# 33-SOC_GENERAL_AND_MCU_GENERAL.net
KiCad netlist of a schematic drawn in Altium Designer
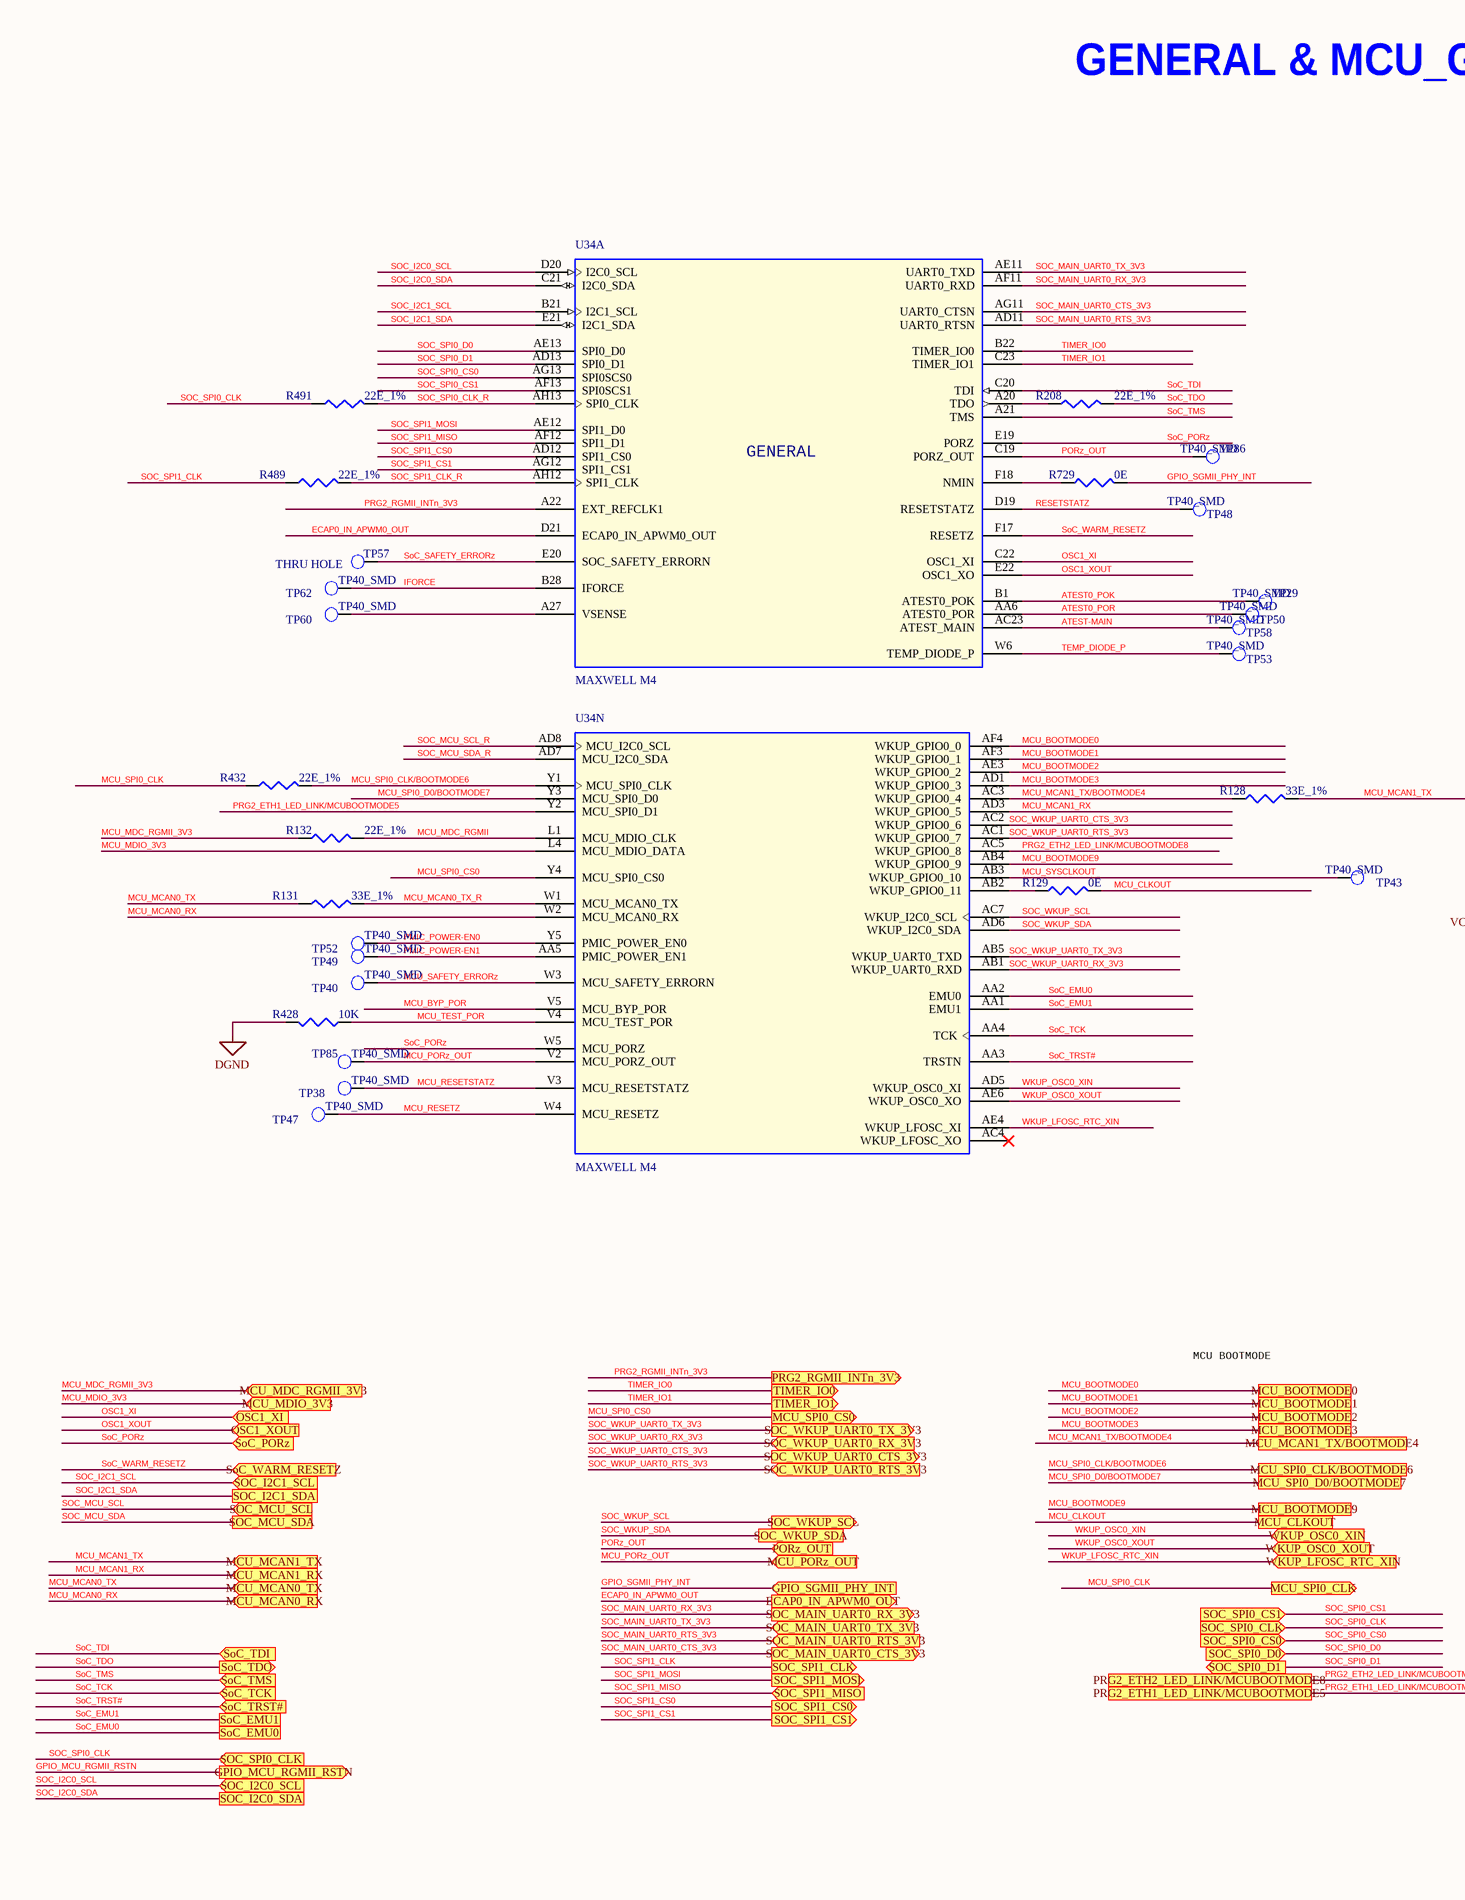
[diagram p0: 33-SOC_GENERAL AND MCU GENERAL.SchDoc, left]
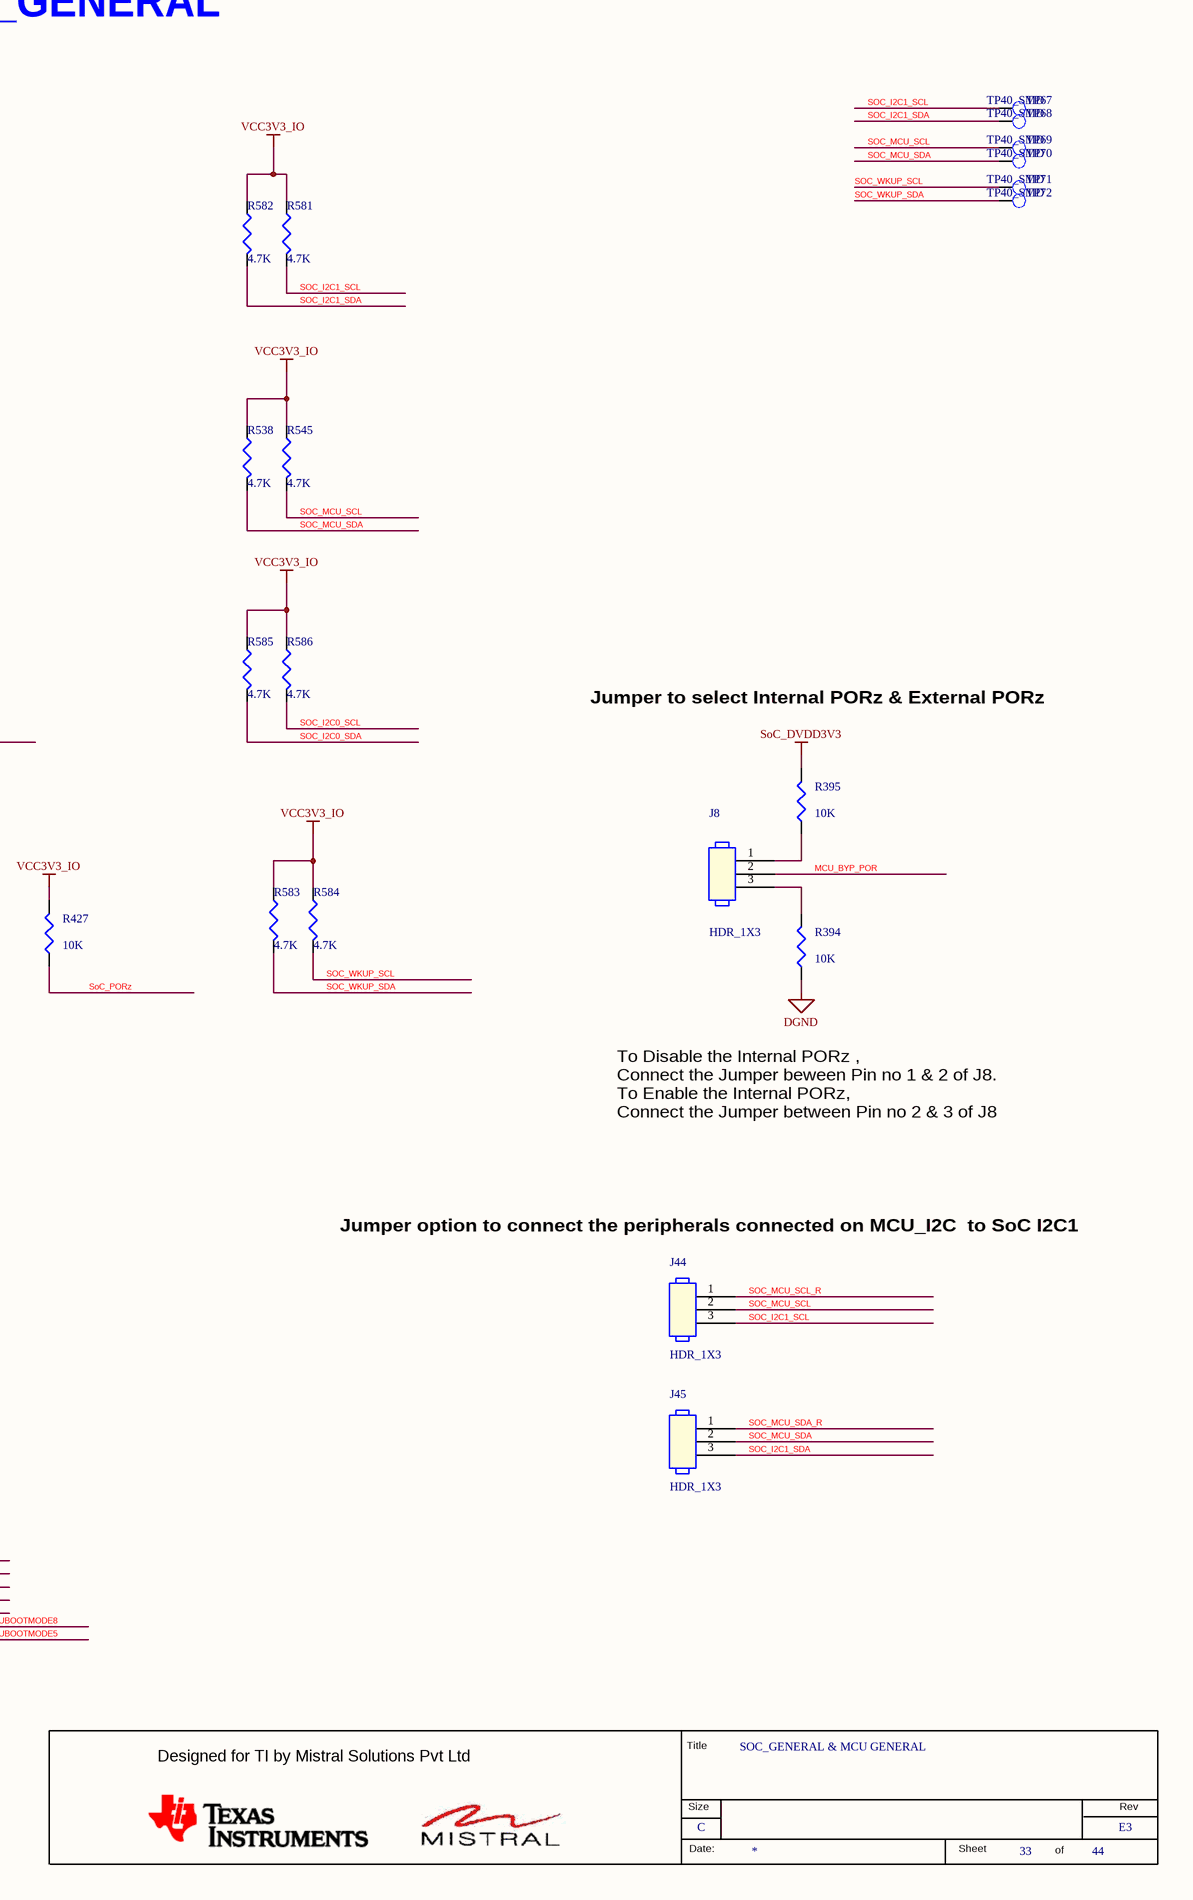
[diagram p1: 33-SOC_GENERAL AND MCU GENERAL.SchDoc, right]

(export (version "E")
  (design (tool "Eeschema 10.0.6"))
  (components
    (comp (ref "J8")
      (value "HDR_1X3")
      (footprint "HDR_3X1_100_S_T")
      (description "HDR 1X3 2.54MM PITCH ST TH")
      (fields (field (name "DISTRIBUTOR_PART_NUMBER") "609-3471-ND") (field (name "VOLTAGE") "NA"))
      (libsource (lib "*") (part "HEADER_3X1"))
    )
    (comp (ref "J44")
      (value "HDR_1X3")
      (footprint "HDR_3X1_100_S_T")
      (description "HDR 1X3 2.54MM PITCH ST TH")
      (fields (field (name "DISTRIBUTOR_PART_NUMBER") "609-3471-ND") (field (name "VOLTAGE") "NA"))
      (libsource (lib "*") (part "HEADER_3X1"))
    )
    (comp (ref "J45")
      (value "HDR_1X3")
      (footprint "HDR_3X1_100_S_T")
      (description "HDR 1X3 2.54MM PITCH ST TH")
      (fields
        (field (name "MISTRAL PART NO") "150016060025-R")
        (field (name "MFR_PART_NUMBER") "68001-403HLF")
      )
      (libsource (lib "*") (part "HEADER_3X1"))
    )
    (comp (ref "R128")
      (value "33E_1%")
      (footprint "RES0402_0-5")
      (description "RES 33E 1/16W 1% 0402")
      (fields (field (name "DISTRIBUTOR_PART_NUMBER") "P33.0LCT-ND") (field (name "VOLTAGE") "NA"))
      (libsource (lib "*") (part "RESISTOR_Dup5"))
    )
    (comp (ref "R129")
      (value "0E")
      (footprint "RES0402_0-5")
      (description "RES 0E 1/16W 0402")
      (fields
        (field (name "MISTRAL PART NO") "110010080019-P")
        (field (name "MFR_PART_NUMBER") "CRCW04020000Z0ED")
      )
      (libsource (lib "*") (part "RESISTOR_Dup4"))
    )
    (comp (ref "R131")
      (value "33E_1%")
      (footprint "RES0402_0-5")
      (description "RES 33E 1/16W 1% 0402")
      (fields
        (field (name "MISTRAL PART NO") "110014110006-R")
        (field (name "MFR_PART_NUMBER") "ERJ-2RKF33R0X")
      )
      (libsource (lib "*") (part "RESISTOR_Dup5"))
    )
    (comp (ref "R132")
      (value "22E_1%")
      (footprint "RES0402")
      (description "RES 22E 1/16W 1% 0402")
      (fields
        (field (name "MISTRAL PART NO") "110009090004-P")
        (field (name "MFR_PART_NUMBER") "RC0402FR-0722RL")
      )
      (libsource (lib "*") (part "RESISTOR_Dup5"))
    )
    (comp (ref "R208")
      (value "22E_1%")
      (footprint "RES0402")
      (description "RES 22E 1/16W 1% 0402")
      (fields
        (field (name "CUST_PART_NUMBER") "4700-80047E")
        (field (name "DISTRIBUTOR_PART_NUMBER") "311-22.0LRCT-ND")
      )
      (libsource (lib "*") (part "RESISTOR_Dup4"))
    )
    (comp (ref "R394")
      (value "10K")
      (footprint "RES0402_0-5")
      (description "RES 10K 1/16W 5% 0402")
      (fields (field (name "DISTRIBUTOR_PART_NUMBER") "311-10KJRCT-ND") (field (name "VOLTAGE") "NA"))
      (libsource (lib "*") (part "RESISTOR_Dup5"))
    )
    (comp (ref "R395")
      (value "10K")
      (footprint "RES0402_0-5")
      (description "RES 10K 1/16W 5% 0402")
      (fields (field (name "DISTRIBUTOR_PART_NUMBER") "311-10KJRCT-ND") (field (name "VOLTAGE") "NA"))
      (libsource (lib "*") (part "RESISTOR_Dup5"))
    )
    (comp (ref "R427")
      (value "10K")
      (footprint "RES0402_0-5")
      (description "RES 10K 1/16W 5% 0402")
      (fields
        (field (name "MISTRAL PART NO") "110009030208-R")
        (field (name "MFR_PART_NUMBER") "RC0402JR-0710KL")
      )
      (libsource (lib "*") (part "RESISTOR_Dup5"))
    )
    (comp (ref "R428")
      (value "10K")
      (footprint "RES0402_0-5")
      (description "RES 10K 1/16W 5% 0402")
      (fields
        (field (name "MISTRAL PART NO") "110009030208-R")
        (field (name "MFR_PART_NUMBER") "RC0402JR-0710KL")
      )
      (libsource (lib "*") (part "RESISTOR_Dup5"))
    )
    (comp (ref "R432")
      (value "22E_1%")
      (footprint "RES0402")
      (description "RES 22E 1/16W 1% 0402")
      (fields
        (field (name "MISTRAL PART NO") "110009090004-P")
        (field (name "MFR_PART_NUMBER") "RC0402FR-0722RL")
      )
      (libsource (lib "*") (part "RESISTOR_Dup4"))
    )
    (comp (ref "R489")
      (value "22E_1%")
      (footprint "RES0402")
      (description "RES 22E 1/16W 1% 0402")
      (fields
        (field (name "CUST_PART_NUMBER") "4700-80047E")
        (field (name "DISTRIBUTOR_PART_NUMBER") "311-22.0LRCT-ND")
      )
      (libsource (lib "*") (part "RESISTOR_Dup4"))
    )
    (comp (ref "R491")
      (value "22E_1%")
      (footprint "RES0402")
      (description "RES 22E 1/16W 1% 0402")
      (fields
        (field (name "CUST_PART_NUMBER") "4700-80047E")
        (field (name "DISTRIBUTOR_PART_NUMBER") "311-22.0LRCT-ND")
      )
      (libsource (lib "*") (part "RESISTOR_Dup4"))
    )
    (comp (ref "R538")
      (value "4.7K")
      (footprint "RES0402")
      (description "RES 4.7K 1/16W 5% 0402")
      (fields (field (name "DISTRIBUTOR_PART_NUMBER") "311-4.7KJRCT-ND") (field (name "VOLTAGE") "NA"))
      (libsource (lib "*") (part "RESISTOR_Dup5"))
    )
    (comp (ref "R545")
      (value "4.7K")
      (footprint "RES0402")
      (description "RES 4.7K 1/16W 5% 0402")
      (fields
        (field (name "MISTRAL PART NO") "110009030792-R")
        (field (name "MFR_PART_NUMBER") "RC0402JR-074K7L")
      )
      (libsource (lib "*") (part "RESISTOR_Dup5"))
    )
    (comp (ref "R581")
      (value "4.7K")
      (footprint "RES0402")
      (description "RES 4.7K 1/16W 5% 0402")
      (fields
        (field (name "MISTRAL PART NO") "110009030792-R")
        (field (name "MFR_PART_NUMBER") "RC0402JR-074K7L")
      )
      (libsource (lib "*") (part "RESISTOR_Dup5"))
    )
    (comp (ref "R582")
      (value "4.7K")
      (footprint "RES0402")
      (description "RES 4.7K 1/16W 5% 0402")
      (fields (field (name "DISTRIBUTOR_PART_NUMBER") "311-4.7KJRCT-ND") (field (name "VOLTAGE") "NA"))
      (libsource (lib "*") (part "RESISTOR_Dup5"))
    )
    (comp (ref "R583")
      (value "4.7K")
      (footprint "RES0402")
      (description "RES 4.7K 1/16W 5% 0402")
      (fields
        (field (name "MISTRAL PART NO") "110009030792-R")
        (field (name "MFR_PART_NUMBER") "RC0402JR-074K7L")
      )
      (libsource (lib "*") (part "RESISTOR_Dup5"))
    )
    (comp (ref "R584")
      (value "4.7K")
      (footprint "RES0402")
      (description "RES 4.7K 1/16W 5% 0402")
      (fields (field (name "DISTRIBUTOR_PART_NUMBER") "311-4.7KJRCT-ND") (field (name "VOLTAGE") "NA"))
      (libsource (lib "*") (part "RESISTOR_Dup5"))
    )
    (comp (ref "R585")
      (value "4.7K")
      (footprint "RES0402")
      (description "RES 4.7K 1/16W 5% 0402")
      (fields (field (name "DISTRIBUTOR_PART_NUMBER") "311-4.7KJRCT-ND") (field (name "VOLTAGE") "NA"))
      (libsource (lib "*") (part "RESISTOR_Dup5"))
    )
    (comp (ref "R586")
      (value "4.7K")
      (footprint "RES0402")
      (description "RES 4.7K 1/16W 5% 0402")
      (fields
        (field (name "MISTRAL PART NO") "110009030792-R")
        (field (name "MFR_PART_NUMBER") "RC0402JR-074K7L")
      )
      (libsource (lib "*") (part "RESISTOR_Dup5"))
    )
    (comp (ref "R729")
      (value "0E")
      (footprint "RES0402_0-5")
      (description "RES 0E 1/16W 0402")
      (fields (field (name "DISTRIBUTOR_PART_NUMBER") "541-0.0JCT-ND") (field (name "VOLTAGE") "NA"))
      (libsource (lib "*") (part "RESISTOR_Dup5"))
    )
    (comp (ref "TP29")
      (value "TP40_SMD")
      (footprint "TP40_SMD")
      (description "TESTPOINT CIR 40 SMD")
      (fields (field (name "MISTRAL PART NO") "130009030933") (field (name "DISTRIBUTOR_PART_NUMBER") "NA"))
      (libsource (lib "*") (part "TESTPOINT"))
    )
    (comp (ref "TP38")
      (value "TP40_SMD")
      (footprint "TP40_SMD")
      (description "TESTPOINT CIR 40 SMD")
      (fields (field (name "MISTRAL PART NO") "130009030933") (field (name "DISTRIBUTOR_PART_NUMBER") "NA"))
      (libsource (lib "*") (part "TESTPOINT"))
    )
    (comp (ref "TP40")
      (value "TP40_SMD")
      (footprint "TP40_SMD")
      (description "TESTPOINT CIR 40 SMD")
      (fields (field (name "MISTRAL PART NO") "130009030933") (field (name "DISTRIBUTOR_PART_NUMBER") "NA"))
      (libsource (lib "*") (part "TESTPOINT"))
    )
    (comp (ref "TP43")
      (value "TP40_SMD")
      (footprint "TP40_SMD")
      (description "TESTPOINT CIR 40 SMD")
      (fields (field (name "DISTRIBUTOR_PART_NUMBER") "NA") (field (name "MISTRAL PART NO") "130009030933"))
      (libsource (lib "*") (part "TESTPOINT"))
    )
    (comp (ref "TP47")
      (value "TP40_SMD")
      (footprint "TP40_SMD")
      (description "TESTPOINT CIR 40 SMD")
      (fields (field (name "MISTRAL PART NO") "130009030933") (field (name "DISTRIBUTOR_PART_NUMBER") "NA"))
      (libsource (lib "*") (part "TESTPOINT"))
    )
    (comp (ref "TP48")
      (value "TP40_SMD")
      (footprint "TP40_SMD")
      (description "TESTPOINT CIR 40 SMD")
      (fields (field (name "MISTRAL PART NO") "130009030933") (field (name "DISTRIBUTOR_PART_NUMBER") "NA"))
      (libsource (lib "*") (part "TESTPOINT"))
    )
    (comp (ref "TP49")
      (value "TP40_SMD")
      (footprint "TP40_SMD")
      (description "TESTPOINT CIR 40 SMD")
      (fields (field (name "VOLTAGE") "NA") (field (name "MISTRAL PART NO") "130009030933"))
      (libsource (lib "*") (part "TESTPOINT"))
    )
    (comp (ref "TP50")
      (value "TP40_SMD")
      (footprint "TP40_SMD")
      (description "TESTPOINT CIR 40 SMD")
      (fields (field (name "VOLTAGE") "NA") (field (name "MISTRAL PART NO") "130009030933"))
      (libsource (lib "*") (part "TESTPOINT"))
    )
    (comp (ref "TP52")
      (value "TP40_SMD")
      (footprint "TP40_SMD")
      (description "TESTPOINT CIR 40 SMD")
      (fields (field (name "MISTRAL PART NO") "130009030933") (field (name "DISTRIBUTOR_PART_NUMBER") "NA"))
      (libsource (lib "*") (part "TESTPOINT"))
    )
    (comp (ref "TP53")
      (value "TP40_SMD")
      (footprint "TP40_SMD")
      (description "TESTPOINT CIR 40 SMD")
      (fields (field (name "VOLTAGE") "NA") (field (name "MISTRAL PART NO") "130009030933"))
      (libsource (lib "*") (part "TESTPOINT"))
    )
    (comp (ref "TP57")
      (value "THRU HOLE")
      (footprint "TP_40X65")
      (description "TESTPOINT 1.0MM DRILL PTH")
      (fields (field (name "DISTRIBUTOR_PART_NUMBER") "NA") (field (name "MFR_PART_NUMBER") "TP_40X65"))
      (libsource (lib "*") (part "TESTPOINT"))
    )
    (comp (ref "TP58")
      (value "TP40_SMD")
      (footprint "TP40_SMD")
      (description "TESTPOINT CIR 40 SMD")
      (fields (field (name "VOLTAGE") "NA") (field (name "MISTRAL PART NO") "130009030933"))
      (libsource (lib "*") (part "TESTPOINT"))
    )
    (comp (ref "TP60")
      (value "TP40_SMD")
      (footprint "TP40_SMD")
      (description "TESTPOINT CIR 40 SMD")
      (fields (field (name "VOLTAGE") "NA") (field (name "MISTRAL PART NO") "130009030933"))
      (libsource (lib "*") (part "TESTPOINT"))
    )
    (comp (ref "TP62")
      (value "TP40_SMD")
      (footprint "TP40_SMD")
      (description "TESTPOINT CIR 40 SMD")
      (fields (field (name "VOLTAGE") "NA") (field (name "MISTRAL PART NO") "130009030933"))
      (libsource (lib "*") (part "TESTPOINT"))
    )
    (comp (ref "TP67")
      (value "TP40_SMD")
      (footprint "TP40_SMD")
      (description "TESTPOINT CIR 40 SMD")
      (fields (field (name "MISTRAL PART NO") "130009030933") (field (name "DISTRIBUTOR_PART_NUMBER") "NA"))
      (libsource (lib "*") (part "TESTPOINT"))
    )
    (comp (ref "TP68")
      (value "TP40_SMD")
      (footprint "TP40_SMD")
      (description "TESTPOINT CIR 40 SMD")
      (fields (field (name "VOLTAGE") "NA") (field (name "MISTRAL PART NO") "130009030933"))
      (libsource (lib "*") (part "TESTPOINT"))
    )
    (comp (ref "TP69")
      (value "TP40_SMD")
      (footprint "TP40_SMD")
      (description "TESTPOINT CIR 40 SMD")
      (fields (field (name "VOLTAGE") "NA") (field (name "MISTRAL PART NO") "130009030933"))
      (libsource (lib "*") (part "TESTPOINT"))
    )
    (comp (ref "TP70")
      (value "TP40_SMD")
      (footprint "TP40_SMD")
      (description "TESTPOINT CIR 40 SMD")
      (fields (field (name "MISTRAL PART NO") "130009030933") (field (name "DISTRIBUTOR_PART_NUMBER") "NA"))
      (libsource (lib "*") (part "TESTPOINT"))
    )
    (comp (ref "TP71")
      (value "TP40_SMD")
      (footprint "TP40_SMD")
      (description "TESTPOINT CIR 40 SMD")
      (fields (field (name "MISTRAL PART NO") "130009030933") (field (name "DISTRIBUTOR_PART_NUMBER") "NA"))
      (libsource (lib "*") (part "TESTPOINT"))
    )
    (comp (ref "TP72")
      (value "TP40_SMD")
      (footprint "TP40_SMD")
      (description "TESTPOINT CIR 40 SMD")
      (fields (field (name "VOLTAGE") "NA") (field (name "MISTRAL PART NO") "130009030933"))
      (libsource (lib "*") (part "TESTPOINT"))
    )
    (comp (ref "TP85")
      (value "TP40_SMD")
      (footprint "TP40_SMD")
      (description "TESTPOINT CIR 40 SMD")
      (fields (field (name "MISTRAL PART NO") "130009030933") (field (name "DISTRIBUTOR_PART_NUMBER") "NA"))
      (libsource (lib "*") (part "TESTPOINT"))
    )
    (comp (ref "TP86")
      (value "TP40_SMD")
      (footprint "TP40_SMD")
      (description "TESTPOINT CIR 40 SMD")
      (fields (field (name "VOLTAGE") "NA") (field (name "MISTRAL PART NO") "130009030933"))
      (libsource (lib "*") (part "TESTPOINT"))
    )
    (comp (ref "U34")
      (value "MAXWELL M4")
      (footprint "BGA784_31-49_910X910_1-7")
      (description "IC MAXWELL MICRO CONTROLLER UNIT BGA784")
      (fields
        (field (name "DISTRIBUTOR_PART_NUMBER") "NA")
        (field (name "MFR_PART_NUMBER") "MAXWELL M4_EVM")
        (field (name "MISTRAL PART NO") "141217100003")
      )
      (libsource (lib "*") (part "AM654X_BGA784"))
    )
  )
  (nets
    (net (code "1") (name "/ATEST-MAIN") (class "Default")
      (node (ref "TP58") (pin "1") (pinfunction "TP_1") (pintype "passive"))
      (node (ref "U34") (pin "AC23") (pinfunction "ATEST_MAIN_AC23") (pintype "passive"))
    )
    (net (code "2") (name "/ATEST0_POK") (class "Default")
      (node (ref "TP29") (pin "1") (pinfunction "TP_1") (pintype "passive"))
      (node (ref "U34") (pin "B1") (pinfunction "ATEST0_POK_B1") (pintype "passive"))
    )
    (net (code "3") (name "/ATEST0_POR") (class "Default")
      (node (ref "TP50") (pin "1") (pinfunction "TP_1") (pintype "passive"))
      (node (ref "U34") (pin "AA6") (pinfunction "ATEST0_POR_AA6") (pintype "passive"))
    )
    (net (code "4") (name "/ECAP0_IN_APWM0_OUT") (class "Default")
      (node (ref "U34") (pin "D21") (pinfunction "ECAP0_IN_APWM0_OUT_D21") (pintype "passive"))
    )
    (net (code "6") (name "/GPIO_SGMII_PHY_INT") (class "Default")
      (node (ref "R729") (pin "2") (pinfunction "2_2") (pintype "passive"))
    )
    (net (code "7") (name "/IFORCE") (class "Default")
      (node (ref "TP62") (pin "1") (pinfunction "TP_1") (pintype "passive"))
      (node (ref "U34") (pin "B28") (pinfunction "IFORCE_B28") (pintype "passive"))
    )
    (net (code "8") (name "/MCU_BOOTMODE0") (class "Default")
      (node (ref "U34") (pin "AF4") (pinfunction "WKUP_GPIO0_0_AF4") (pintype "passive"))
    )
    (net (code "9") (name "/MCU_BOOTMODE1") (class "Default")
      (node (ref "U34") (pin "AF3") (pinfunction "WKUP_GPIO0_1_AF3") (pintype "passive"))
    )
    (net (code "10") (name "/MCU_BOOTMODE2") (class "Default")
      (node (ref "U34") (pin "AE3") (pinfunction "WKUP_GPIO0_2_AE3") (pintype "passive"))
    )
    (net (code "11") (name "/MCU_BOOTMODE3") (class "Default")
      (node (ref "U34") (pin "AD1") (pinfunction "WKUP_GPIO0_3_AD1") (pintype "passive"))
    )
    (net (code "12") (name "/MCU_BOOTMODE9") (class "Default")
      (node (ref "U34") (pin "AB4") (pinfunction "WKUP_GPIO0_9_AB4") (pintype "passive"))
    )
    (net (code "13") (name "/MCU_BYP_POR") (class "Default")
      (node (ref "J8") (pin "2") (pinfunction "2_2") (pintype "passive"))
      (node (ref "U34") (pin "V5") (pinfunction "MCU_BYP_POR_V5") (pintype "passive"))
    )
    (net (code "14") (name "/MCU_CLKOUT") (class "Default")
      (node (ref "R129") (pin "2") (pinfunction "2_2") (pintype "passive"))
    )
    (net (code "15") (name "/MCU_MCAN0_RX") (class "Default")
      (node (ref "U34") (pin "W2") (pinfunction "MCU_MCAN0_RX_W2") (pintype "passive"))
    )
    (net (code "16") (name "/MCU_MCAN0_TX") (class "Default")
      (node (ref "R131") (pin "1") (pinfunction "1_1") (pintype "passive"))
    )
    (net (code "17") (name "/MCU_MCAN0_TX_R") (class "Default")
      (node (ref "R131") (pin "2") (pinfunction "2_2") (pintype "passive"))
      (node (ref "U34") (pin "W1") (pinfunction "MCU_MCAN0_TX_W1") (pintype "passive"))
    )
    (net (code "18") (name "/MCU_MCAN1_RX") (class "Default")
      (node (ref "U34") (pin "AD3") (pinfunction "WKUP_GPIO0_5_AD3") (pintype "passive"))
    )
    (net (code "19") (name "/MCU_MCAN1_TX") (class "Default")
      (node (ref "R128") (pin "2") (pinfunction "2_2") (pintype "passive"))
    )
    (net (code "20") (name "/MCU_MCAN1_TX{slash}BOOTMODE4") (class "Default")
      (node (ref "R128") (pin "1") (pinfunction "1_1") (pintype "passive"))
      (node (ref "U34") (pin "AC3") (pinfunction "WKUP_GPIO0_4_AC3") (pintype "passive"))
    )
    (net (code "21") (name "/MCU_MDC_RGMII") (class "Default")
      (node (ref "R132") (pin "2") (pinfunction "2_2") (pintype "passive"))
      (node (ref "U34") (pin "L1") (pinfunction "MCU_MDIO_CLK_L1") (pintype "passive"))
    )
    (net (code "22") (name "/MCU_MDC_RGMII_3V3") (class "Default")
      (node (ref "R132") (pin "1") (pinfunction "1_1") (pintype "passive"))
    )
    (net (code "23") (name "/MCU_MDIO_3V3") (class "Default")
      (node (ref "U34") (pin "L4") (pinfunction "MCU_MDIO_DATA_L4") (pintype "passive"))
    )
    (net (code "24") (name "/MCU_PORz_OUT") (class "Default")
      (node (ref "TP85") (pin "1") (pinfunction "TP_1") (pintype "passive"))
      (node (ref "U34") (pin "V2") (pinfunction "MCU_PORZ_OUT_V2") (pintype "passive"))
    )
    (net (code "25") (name "/MCU_RESETSTATZ") (class "Default")
      (node (ref "TP38") (pin "1") (pinfunction "TP_1") (pintype "passive"))
      (node (ref "U34") (pin "V3") (pinfunction "MCU_RESETSTATZ_V3") (pintype "passive"))
    )
    (net (code "26") (name "/MCU_RESETZ") (class "Default")
      (node (ref "TP47") (pin "1") (pinfunction "TP_1") (pintype "passive"))
      (node (ref "U34") (pin "W4") (pinfunction "MCU_RESETZ_W4") (pintype "passive"))
    )
    (net (code "27") (name "/MCU_SAFETY_ERRORz") (class "Default")
      (node (ref "TP40") (pin "1") (pinfunction "TP_1") (pintype "passive"))
      (node (ref "U34") (pin "W3") (pinfunction "MCU_SAFETY_ERRORN_W3") (pintype "passive"))
    )
    (net (code "28") (name "/MCU_SPI0_CLK") (class "Default")
      (node (ref "R432") (pin "1") (pinfunction "1_1") (pintype "passive"))
    )
    (net (code "29") (name "/MCU_SPI0_CLK{slash}BOOTMODE6") (class "Default")
      (node (ref "R432") (pin "2") (pinfunction "2_2") (pintype "passive"))
      (node (ref "U34") (pin "Y1") (pinfunction "MCU_SPI0_CLK_Y1") (pintype "passive"))
    )
    (net (code "30") (name "/MCU_SPI0_CS0") (class "Default")
      (node (ref "U34") (pin "Y4") (pinfunction "MCU_SPI0_CS0_Y4") (pintype "passive"))
    )
    (net (code "31") (name "/MCU_SPI0_D0{slash}BOOTMODE7") (class "Default")
      (node (ref "U34") (pin "Y3") (pinfunction "MCU_SPI0_D0_Y3") (pintype "passive"))
    )
    (net (code "32") (name "/MCU_SYSCLKOUT") (class "Default")
      (node (ref "TP43") (pin "1") (pinfunction "TP_1") (pintype "passive"))
      (node (ref "U34") (pin "AB3") (pinfunction "WKUP_GPIO0_10_AB3") (pintype "passive"))
    )
    (net (code "33") (name "/MCU_TEST_POR") (class "Default")
      (node (ref "R428") (pin "1") (pinfunction "1_1") (pintype "passive"))
      (node (ref "U34") (pin "V4") (pinfunction "MCU_TEST_POR_V4") (pintype "passive"))
    )
    (net (code "34") (name "/OSC1_XI") (class "Default")
      (node (ref "U34") (pin "C22") (pinfunction "OSC1_XI_C22") (pintype "passive"))
    )
    (net (code "35") (name "/OSC1_XOUT") (class "Default")
      (node (ref "U34") (pin "E22") (pinfunction "OSC1_XO_E22") (pintype "passive"))
    )
    (net (code "36") (name "/PMIC_POWER-EN0") (class "Default")
      (node (ref "TP52") (pin "1") (pinfunction "TP_1") (pintype "passive"))
      (node (ref "U34") (pin "Y5") (pinfunction "PMIC_POWER_EN0_Y5") (pintype "passive"))
    )
    (net (code "37") (name "/PMIC_POWER-EN1") (class "Default")
      (node (ref "TP49") (pin "1") (pinfunction "TP_1") (pintype "passive"))
      (node (ref "U34") (pin "AA5") (pinfunction "PMIC_POWER_EN1_AA5") (pintype "passive"))
    )
    (net (code "38") (name "/PORz_OUT") (class "Default")
      (node (ref "TP86") (pin "1") (pinfunction "TP_1") (pintype "passive"))
      (node (ref "U34") (pin "C19") (pinfunction "PORZ_OUT_C19") (pintype "passive"))
    )
    (net (code "39") (name "/PRG2_ETH1_LED_LINK{slash}MCUBOOTMODE5") (class "Default")
      (node (ref "U34") (pin "Y2") (pinfunction "MCU_SPI0_D1_Y2") (pintype "passive"))
    )
    (net (code "40") (name "/PRG2_ETH2_LED_LINK{slash}MCUBOOTMODE8") (class "Default")
      (node (ref "U34") (pin "AC5") (pinfunction "WKUP_GPIO0_8_AC5") (pintype "passive"))
    )
    (net (code "41") (name "/PRG2_RGMII_INTn_3V3") (class "Default")
      (node (ref "U34") (pin "A22") (pinfunction "EXT_REFCLK1_A22") (pintype "passive"))
    )
    (net (code "42") (name "/RESETSTATZ") (class "Default")
      (node (ref "TP48") (pin "1") (pinfunction "TP_1") (pintype "passive"))
      (node (ref "U34") (pin "D19") (pinfunction "RESETSTATZ_D19") (pintype "passive"))
    )
    (net (code "43") (name "/SOC_I2C0_SCL") (class "Default")
      (node (ref "R586") (pin "2") (pinfunction "2_2") (pintype "passive"))
      (node (ref "U34") (pin "D20") (pinfunction "I2C0_SCL_D20") (pintype "input"))
    )
    (net (code "44") (name "/SOC_I2C0_SDA") (class "Default")
      (node (ref "R585") (pin "2") (pinfunction "2_2") (pintype "passive"))
      (node (ref "U34") (pin "C21") (pinfunction "I2C0_SDA_C21") (pintype "bidirectional"))
    )
    (net (code "45") (name "/SOC_I2C1_SCL") (class "Default")
      (node (ref "J44") (pin "3") (pinfunction "3_3") (pintype "passive"))
      (node (ref "R581") (pin "2") (pinfunction "2_2") (pintype "passive"))
      (node (ref "TP67") (pin "1") (pinfunction "TP_1") (pintype "passive"))
      (node (ref "U34") (pin "B21") (pinfunction "I2C1_SCL_B21") (pintype "input"))
    )
    (net (code "46") (name "/SOC_I2C1_SDA") (class "Default")
      (node (ref "J45") (pin "3") (pinfunction "3_3") (pintype "passive"))
      (node (ref "R582") (pin "2") (pinfunction "2_2") (pintype "passive"))
      (node (ref "TP68") (pin "1") (pinfunction "TP_1") (pintype "passive"))
      (node (ref "U34") (pin "E21") (pinfunction "I2C1_SDA_E21") (pintype "bidirectional"))
    )
    (net (code "47") (name "/SOC_MAIN_UART0_CTS_3V3") (class "Default")
      (node (ref "U34") (pin "AG11") (pinfunction "UART0_CTSN_AG11") (pintype "passive"))
    )
    (net (code "48") (name "/SOC_MAIN_UART0_RTS_3V3") (class "Default")
      (node (ref "U34") (pin "AD11") (pinfunction "UART0_RTSN_AD11") (pintype "passive"))
    )
    (net (code "49") (name "/SOC_MAIN_UART0_RX_3V3") (class "Default")
      (node (ref "U34") (pin "AF11") (pinfunction "UART0_RXD_AF11") (pintype "passive"))
    )
    (net (code "50") (name "/SOC_MAIN_UART0_TX_3V3") (class "Default")
      (node (ref "U34") (pin "AE11") (pinfunction "UART0_TXD_AE11") (pintype "passive"))
    )
    (net (code "51") (name "/SOC_MCU_SCL") (class "Default")
      (node (ref "J44") (pin "2") (pinfunction "2_2") (pintype "passive"))
      (node (ref "R545") (pin "2") (pinfunction "2_2") (pintype "passive"))
      (node (ref "TP69") (pin "1") (pinfunction "TP_1") (pintype "passive"))
    )
    (net (code "52") (name "/SOC_MCU_SCL_R") (class "Default")
      (node (ref "J44") (pin "1") (pinfunction "1_1") (pintype "passive"))
      (node (ref "U34") (pin "AD8") (pinfunction "MCU_I2C0_SCL_AD8") (pintype "passive"))
    )
    (net (code "53") (name "/SOC_MCU_SDA") (class "Default")
      (node (ref "J45") (pin "2") (pinfunction "2_2") (pintype "passive"))
      (node (ref "R538") (pin "2") (pinfunction "2_2") (pintype "passive"))
      (node (ref "TP70") (pin "1") (pinfunction "TP_1") (pintype "passive"))
    )
    (net (code "54") (name "/SOC_MCU_SDA_R") (class "Default")
      (node (ref "J45") (pin "1") (pinfunction "1_1") (pintype "passive"))
      (node (ref "U34") (pin "AD7") (pinfunction "MCU_I2C0_SDA_AD7") (pintype "passive"))
    )
    (net (code "55") (name "/SOC_SPI0_CLK") (class "Default")
      (node (ref "R491") (pin "1") (pinfunction "1_1") (pintype "passive"))
    )
    (net (code "56") (name "/SOC_SPI0_CLK_R") (class "Default")
      (node (ref "R491") (pin "2") (pinfunction "2_2") (pintype "passive"))
      (node (ref "U34") (pin "AH13") (pinfunction "SPI0_CLK_AH13") (pintype "passive"))
    )
    (net (code "57") (name "/SOC_SPI0_CS0") (class "Default")
      (node (ref "U34") (pin "AG13") (pinfunction "SPI0SCS0_AG13") (pintype "passive"))
    )
    (net (code "58") (name "/SOC_SPI0_CS1") (class "Default")
      (node (ref "U34") (pin "AF13") (pinfunction "SPI0SCS1_AF13") (pintype "passive"))
    )
    (net (code "59") (name "/SOC_SPI0_D0") (class "Default")
      (node (ref "U34") (pin "AE13") (pinfunction "SPI0_D0_AE13") (pintype "passive"))
    )
    (net (code "60") (name "/SOC_SPI0_D1") (class "Default")
      (node (ref "U34") (pin "AD13") (pinfunction "SPI0_D1_AD13") (pintype "passive"))
    )
    (net (code "61") (name "/SOC_SPI1_CLK") (class "Default")
      (node (ref "R489") (pin "1") (pinfunction "1_1") (pintype "passive"))
    )
    (net (code "62") (name "/SOC_SPI1_CLK_R") (class "Default")
      (node (ref "R489") (pin "2") (pinfunction "2_2") (pintype "passive"))
      (node (ref "U34") (pin "AH12") (pinfunction "SPI1_CLK_AH12") (pintype "passive"))
    )
    (net (code "63") (name "/SOC_SPI1_CS0") (class "Default")
      (node (ref "U34") (pin "AD12") (pinfunction "SPI1_CS0_AD12") (pintype "passive"))
    )
    (net (code "64") (name "/SOC_SPI1_CS1") (class "Default")
      (node (ref "U34") (pin "AG12") (pinfunction "SPI1_CS1_AG12") (pintype "passive"))
    )
    (net (code "65") (name "/SOC_SPI1_MISO") (class "Default")
      (node (ref "U34") (pin "AF12") (pinfunction "SPI1_D1_AF12") (pintype "passive"))
    )
    (net (code "66") (name "/SOC_SPI1_MOSI") (class "Default")
      (node (ref "U34") (pin "AE12") (pinfunction "SPI1_D0_AE12") (pintype "passive"))
    )
    (net (code "67") (name "/SOC_WKUP_SCL") (class "Default")
      (node (ref "R584") (pin "2") (pinfunction "2_2") (pintype "passive"))
      (node (ref "TP71") (pin "1") (pinfunction "TP_1") (pintype "passive"))
      (node (ref "U34") (pin "AC7") (pinfunction "WKUP_I2C0_SCL_AC7") (pintype "passive"))
    )
    (net (code "68") (name "/SOC_WKUP_SDA") (class "Default")
      (node (ref "R583") (pin "2") (pinfunction "2_2") (pintype "passive"))
      (node (ref "TP72") (pin "1") (pinfunction "TP_1") (pintype "passive"))
      (node (ref "U34") (pin "AD6") (pinfunction "WKUP_I2C0_SDA_AD6") (pintype "passive"))
    )
    (net (code "69") (name "/SOC_WKUP_UART0_CTS_3V3") (class "Default")
      (node (ref "U34") (pin "AC2") (pinfunction "WKUP_GPIO0_6_AC2") (pintype "passive"))
    )
    (net (code "70") (name "/SOC_WKUP_UART0_RTS_3V3") (class "Default")
      (node (ref "U34") (pin "AC1") (pinfunction "WKUP_GPIO0_7_AC1") (pintype "passive"))
    )
    (net (code "71") (name "/SOC_WKUP_UART0_RX_3V3") (class "Default")
      (node (ref "U34") (pin "AB1") (pinfunction "WKUP_UART0_RXD_AB1") (pintype "passive"))
    )
    (net (code "72") (name "/SOC_WKUP_UART0_TX_3V3") (class "Default")
      (node (ref "U34") (pin "AB5") (pinfunction "WKUP_UART0_TXD_AB5") (pintype "passive"))
    )
    (net (code "73") (name "/SoC_EMU0") (class "Default")
      (node (ref "U34") (pin "AA2") (pinfunction "EMU0_AA2") (pintype "passive"))
    )
    (net (code "74") (name "/SoC_EMU1") (class "Default")
      (node (ref "U34") (pin "AA1") (pinfunction "EMU1_AA1") (pintype "passive"))
    )
    (net (code "75") (name "/SoC_PORz") (class "Default")
      (node (ref "R427") (pin "1") (pinfunction "1_1") (pintype "passive"))
      (node (ref "U34") (pin "E19") (pinfunction "PORZ_E19") (pintype "passive"))
      (node (ref "U34") (pin "W5") (pinfunction "MCU_PORZ_W5") (pintype "passive"))
    )
    (net (code "76") (name "/SoC_SAFETY_ERRORz") (class "Default")
      (node (ref "TP57") (pin "1") (pinfunction "TP_1") (pintype "passive"))
      (node (ref "U34") (pin "E20") (pinfunction "SOC_SAFETY_ERRORN_E20") (pintype "passive"))
    )
    (net (code "77") (name "/SoC_TCK") (class "Default")
      (node (ref "U34") (pin "AA4") (pinfunction "TCK_AA4") (pintype "passive"))
    )
    (net (code "78") (name "/SoC_TDI") (class "Default")
      (node (ref "U34") (pin "C20") (pinfunction "TDI_C20") (pintype "input"))
    )
    (net (code "79") (name "/SoC_TDO") (class "Default")
      (node (ref "R208") (pin "2") (pinfunction "2_2") (pintype "passive"))
    )
    (net (code "80") (name "/SoC_TMS") (class "Default")
      (node (ref "U34") (pin "A21") (pinfunction "TMS_A21") (pintype "passive"))
    )
    (net (code "81") (name "/SoC_TRST#") (class "Default")
      (node (ref "U34") (pin "AA3") (pinfunction "TRSTN_AA3") (pintype "passive"))
    )
    (net (code "82") (name "/SoC_WARM_RESETZ") (class "Default")
      (node (ref "U34") (pin "F17") (pinfunction "RESETZ_F17") (pintype "passive"))
    )
    (net (code "83") (name "/TEMP_DIODE_P") (class "Default")
      (node (ref "TP53") (pin "1") (pinfunction "TP_1") (pintype "passive"))
      (node (ref "U34") (pin "W6") (pinfunction "TEMP_DIODE_P_W6") (pintype "passive"))
    )
    (net (code "84") (name "/TIMER_IO0") (class "Default")
      (node (ref "U34") (pin "B22") (pinfunction "TIMER_IO0_B22") (pintype "passive"))
    )
    (net (code "85") (name "/TIMER_IO1") (class "Default")
      (node (ref "U34") (pin "C23") (pinfunction "TIMER_IO1_C23") (pintype "passive"))
    )
    (net (code "86") (name "/WKUP_LFOSC_RTC_XIN") (class "Default")
      (node (ref "U34") (pin "AE4") (pinfunction "WKUP_LFOSC_XI_AE4") (pintype "passive"))
    )
    (net (code "87") (name "/WKUP_OSC0_XIN") (class "Default")
      (node (ref "U34") (pin "AD5") (pinfunction "WKUP_OSC0_XI_AD5") (pintype "passive"))
    )
    (net (code "88") (name "/WKUP_OSC0_XOUT") (class "Default")
      (node (ref "U34") (pin "AE6") (pinfunction "WKUP_OSC0_XO_AE6") (pintype "passive"))
    )
    (net (code "89") (name "DGND") (class "Default")
      (node (ref "R394") (pin "1") (pinfunction "1_1") (pintype "passive"))
      (node (ref "R428") (pin "2") (pinfunction "2_2") (pintype "passive"))
    )
    (net (code "90") (name "Net-(J8-Pad1)") (class "Default")
      (node (ref "J8") (pin "1") (pinfunction "1_1") (pintype "passive"))
      (node (ref "R395") (pin "1") (pinfunction "1_1") (pintype "passive"))
    )
    (net (code "91") (name "Net-(J8-Pad3)") (class "Default")
      (node (ref "J8") (pin "3") (pinfunction "3_3") (pintype "passive"))
      (node (ref "R394") (pin "2") (pinfunction "2_2") (pintype "passive"))
    )
    (net (code "92") (name "Net-(TP60-TP)") (class "Default")
      (node (ref "TP60") (pin "1") (pinfunction "TP_1") (pintype "passive"))
      (node (ref "U34") (pin "A27") (pinfunction "VSENSE_A27") (pintype "passive"))
    )
    (net (code "93") (name "Net-(U34A-NMIN)") (class "Default")
      (node (ref "R729") (pin "1") (pinfunction "1_1") (pintype "passive"))
      (node (ref "U34") (pin "F18") (pinfunction "NMIN_F18") (pintype "passive"))
    )
    (net (code "94") (name "Net-(U34A-TDO)") (class "Default")
      (node (ref "R208") (pin "1") (pinfunction "1_1") (pintype "passive"))
      (node (ref "U34") (pin "A20") (pinfunction "TDO_A20") (pintype "output"))
    )
    (net (code "95") (name "Net-(U34N-WKUP_GPIO0_11)") (class "Default")
      (node (ref "R129") (pin "1") (pinfunction "1_1") (pintype "passive"))
      (node (ref "U34") (pin "AB2") (pinfunction "WKUP_GPIO0_11_AB2") (pintype "passive"))
    )
    (net (code "96") (name "SoC_DVDD3V3") (class "Default")
      (node (ref "R395") (pin "2") (pinfunction "2_2") (pintype "passive"))
    )
    (net (code "97") (name "VCC3V3_IO") (class "Default")
      (node (ref "R427") (pin "2") (pinfunction "2_2") (pintype "passive"))
      (node (ref "R538") (pin "1") (pinfunction "1_1") (pintype "passive"))
      (node (ref "R545") (pin "1") (pinfunction "1_1") (pintype "passive"))
      (node (ref "R581") (pin "1") (pinfunction "1_1") (pintype "passive"))
      (node (ref "R582") (pin "1") (pinfunction "1_1") (pintype "passive"))
      (node (ref "R583") (pin "1") (pinfunction "1_1") (pintype "passive"))
      (node (ref "R584") (pin "1") (pinfunction "1_1") (pintype "passive"))
      (node (ref "R585") (pin "1") (pinfunction "1_1") (pintype "passive"))
      (node (ref "R586") (pin "1") (pinfunction "1_1") (pintype "passive"))
    )
    (net (code "98") (name "unconnected-(U34N-WKUP_LFOSC_XO-PadAC4)") (class "Default")
      (node (ref "U34") (pin "AC4") (pinfunction "WKUP_LFOSC_XO_AC4") (pintype "passive+no_connect"))
    )
  )
)
